# warship_demo_1.net
KiCad netlist of a schematic drawn in Altium Designer
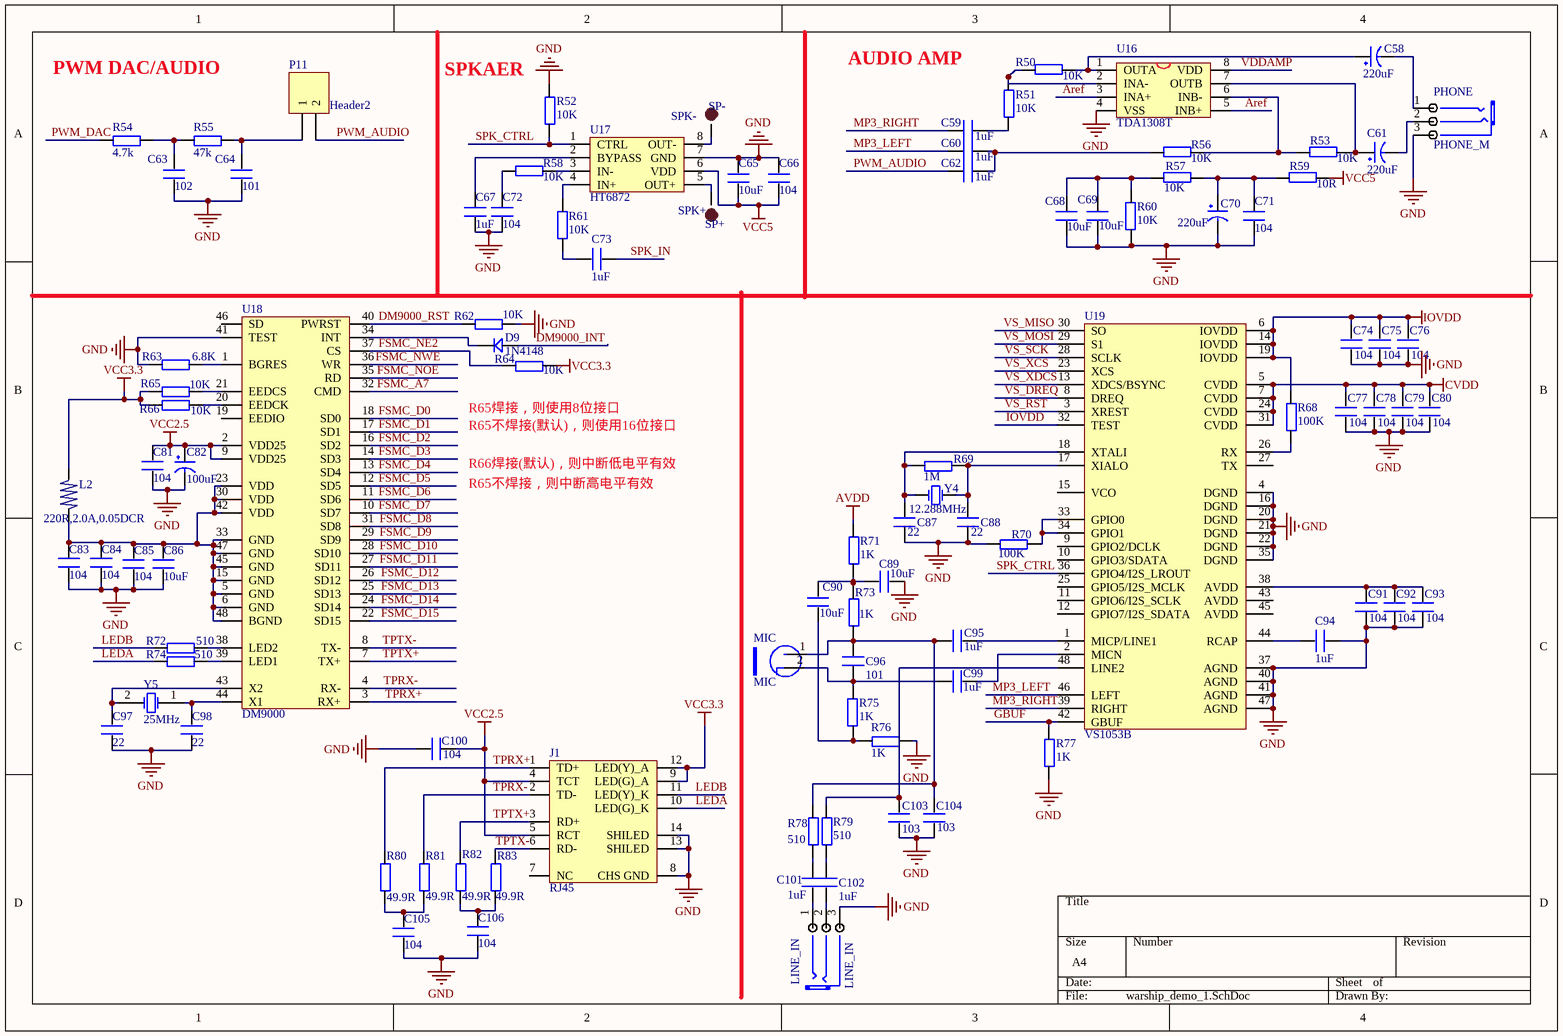
[diagram p0: warship_demo_1.SchDoc]

(export (version "E")
  (design (tool "Eeschema 10.0.6"))
  (components
    (comp (ref "C58") (value "220uF") (footprint "CC6.56.5") (libsource (lib "") (part "CAP_1")))
    (comp (ref "C59") (value "1uF") (footprint "0603P") (libsource (lib "WarShip V3 STM32103封装库") (part "C")))
    (comp (ref "C60") (value "1uF") (footprint "0603P") (libsource (lib "WarShip V3 STM32103封装库") (part "C")))
    (comp (ref "C61") (value "220uF") (footprint "CC6.56.5") (libsource (lib "") (part "CAP_1")))
    (comp (ref "C62") (value "1uF") (footprint "0603P") (libsource (lib "WarShip V3 STM32103封装库") (part "C")))
    (comp (ref "C63") (value "102") (footprint "0603P") (libsource (lib "WarShip V3 STM32103封装库") (part "C")))
    (comp (ref "C64") (value "101") (footprint "0603P") (libsource (lib "WarShip V3 STM32103封装库") (part "C")))
    (comp (ref "C65")
      (value "10uF")
      (footprint "0603P")
      (libsource (lib "WarShip V3 STM32103封装库") (part "C"))
    )
    (comp (ref "C66") (value "104") (footprint "0603P") (libsource (lib "WarShip V3 STM32103封装库") (part "C")))
    (comp (ref "C67") (value "1uF") (footprint "0603P") (libsource (lib "WarShip V3 STM32103封装库") (part "C")))
    (comp (ref "C68")
      (value "10uF")
      (footprint "0603P")
      (libsource (lib "WarShip V3 STM32103封装库") (part "C"))
    )
    (comp (ref "C69")
      (value "10uF")
      (footprint "0603P")
      (libsource (lib "WarShip V3 STM32103封装库") (part "C"))
    )
    (comp (ref "C70")
      (value "220uF")
      (footprint "CC6.56.5")
      (libsource (lib "WarShip V3 STM32103封装库") (part "CAP"))
    )
    (comp (ref "C71") (value "104") (footprint "0603P") (libsource (lib "WarShip V3 STM32103封装库") (part "C")))
    (comp (ref "C72") (value "104") (footprint "0603P") (libsource (lib "WarShip V3 STM32103封装库") (part "C")))
    (comp (ref "C73") (value "1uF") (footprint "0603P") (libsource (lib "WarShip V3 STM32103封装库") (part "C")))
    (comp (ref "C74") (value "104") (footprint "0603P") (libsource (lib "MP3模块封装库") (part "C")))
    (comp (ref "C75") (value "104") (footprint "0603P") (libsource (lib "MP3模块封装库") (part "C")))
    (comp (ref "C76") (value "104") (footprint "0603P") (libsource (lib "MP3模块封装库") (part "C")))
    (comp (ref "C77") (value "104") (footprint "0603P") (libsource (lib "MP3模块封装库") (part "C")))
    (comp (ref "C78") (value "104") (footprint "0603P") (libsource (lib "MP3模块封装库") (part "C")))
    (comp (ref "C79") (value "104") (footprint "0603P") (libsource (lib "MP3模块封装库") (part "C")))
    (comp (ref "C80") (value "104") (footprint "0603P") (libsource (lib "MP3模块封装库") (part "C")))
    (comp (ref "C81") (value "104") (footprint "0603P") (libsource (lib "WarShip V3 STM32103封装库") (part "C")))
    (comp (ref "C82")
      (value "100uF")
      (footprint "CC6.56.5")
      (libsource (lib "WarShip V3 STM32103封装库") (part "CAP"))
    )
    (comp (ref "C83") (value "104") (footprint "0603P") (libsource (lib "WarShip V3 STM32103封装库") (part "C")))
    (comp (ref "C84") (value "104") (footprint "0603P") (libsource (lib "WarShip V3 STM32103封装库") (part "C")))
    (comp (ref "C85") (value "104") (footprint "0603P") (libsource (lib "WarShip V3 STM32103封装库") (part "C")))
    (comp (ref "C86")
      (value "10uF")
      (footprint "0603P")
      (libsource (lib "WarShip V3 STM32103封装库") (part "C"))
    )
    (comp (ref "C87") (value "22") (footprint "0603P") (libsource (lib "MP3模块封装库") (part "C")))
    (comp (ref "C88") (value "22") (footprint "0603P") (libsource (lib "MP3模块封装库") (part "C")))
    (comp (ref "C89") (value "10uF") (footprint "0603P") (libsource (lib "MP3模块封装库") (part "C")))
    (comp (ref "C90") (value "10uF") (footprint "0603P") (libsource (lib "MP3模块封装库") (part "C")))
    (comp (ref "C91") (value "104") (footprint "0603P") (libsource (lib "MP3模块封装库") (part "C")))
    (comp (ref "C92") (value "104") (footprint "0603P") (libsource (lib "MP3模块封装库") (part "C")))
    (comp (ref "C93") (value "104") (footprint "0603P") (libsource (lib "MP3模块封装库") (part "C")))
    (comp (ref "C94") (value "1uF") (footprint "0603P") (libsource (lib "MP3模块封装库") (part "C")))
    (comp (ref "C95") (value "1uF") (footprint "0603P") (libsource (lib "MP3模块封装库") (part "C")))
    (comp (ref "C96") (value "101") (footprint "0603P") (libsource (lib "MP3模块封装库") (part "C")))
    (comp (ref "C97") (value "22") (footprint "0603P") (libsource (lib "WarShip V3 STM32103封装库") (part "C")))
    (comp (ref "C98") (value "22") (footprint "0603P") (libsource (lib "WarShip V3 STM32103封装库") (part "C")))
    (comp (ref "C99") (value "1uF") (footprint "0603P") (libsource (lib "MP3模块封装库") (part "C")))
    (comp (ref "C100")
      (value "104")
      (footprint "0603P")
      (libsource (lib "WarShip V3 STM32103封装库") (part "C"))
    )
    (comp (ref "C101") (value "1uF") (footprint "0603P") (libsource (lib "MP3模块封装库") (part "C")))
    (comp (ref "C102") (value "1uF") (footprint "0603P") (libsource (lib "MP3模块封装库") (part "C")))
    (comp (ref "C103") (value "103") (footprint "0603P") (libsource (lib "MP3模块封装库") (part "C")))
    (comp (ref "C104") (value "103") (footprint "0603P") (libsource (lib "MP3模块封装库") (part "C")))
    (comp (ref "C105")
      (value "104")
      (footprint "0603P")
      (libsource (lib "WarShip V3 STM32103封装库") (part "C"))
    )
    (comp (ref "C106")
      (value "104")
      (footprint "0603P")
      (libsource (lib "WarShip V3 STM32103封装库") (part "C"))
    )
    (comp (ref "D9")
      (value "1N4148")
      (footprint "DIODE_SOP")
      (libsource (lib "WarShip V3 STM32103封装库") (part "D"))
    )
    (comp (ref "J1")
      (value "RJ45")
      (footprint "HR911105A")
      (libsource (lib "WarShip V3 STM32103封装库") (part "HR911105"))
    )
    (comp (ref "L2")
      (value "220R,2.0A,0.05DCR")
      (footprint "0603P")
      (libsource (lib "WarShip V3 STM32103封装库") (part "L"))
    )
    (comp (ref "LINE_IN")
      (value "LINE_IN")
      (footprint "PHONE_ST")
      (libsource (lib "MP3模块封装库") (part "PHONE_M"))
    )
    (comp (ref "MIC") (value "MIC") (footprint "MIC") (libsource (lib "MP3模块封装库") (part "MIC")))
    (comp (ref "P11")
      (value "Header2")
      (footprint "HDR1X2")
      (description "Header, 2-Pin")
      (fields (field (name "PUBLISHER") "Altium Limited"))
      (libsource (lib "WarShip V3 STM32103封装库") (part "Header 2"))
    )
    (comp (ref "PHONE")
      (value "PHONE_M")
      (footprint "PHONE_ST")
      (libsource (lib "WarShip V3 STM32103封装库") (part "PHONE_M"))
    )
    (comp (ref "R50") (value "10K") (footprint "0603P") (libsource (lib "WarShip V3 STM32103封装库") (part "R")))
    (comp (ref "R51") (value "10K") (footprint "0603P") (libsource (lib "WarShip V3 STM32103封装库") (part "R")))
    (comp (ref "R52") (value "10K") (footprint "0603P") (libsource (lib "WarShip V3 STM32103封装库") (part "R")))
    (comp (ref "R53") (value "10K") (footprint "0603P") (libsource (lib "WarShip V3 STM32103封装库") (part "R")))
    (comp (ref "R54")
      (value "4.7k")
      (footprint "0603P")
      (libsource (lib "WarShip V3 STM32103封装库") (part "R"))
    )
    (comp (ref "R55") (value "47k") (footprint "0603P") (libsource (lib "WarShip V3 STM32103封装库") (part "R")))
    (comp (ref "R56") (value "10K") (footprint "0603P") (libsource (lib "WarShip V3 STM32103封装库") (part "R")))
    (comp (ref "R57") (value "10K") (footprint "0603P") (libsource (lib "WarShip V3 STM32103封装库") (part "R")))
    (comp (ref "R58") (value "10K") (footprint "0603P") (libsource (lib "WarShip V3 STM32103封装库") (part "R")))
    (comp (ref "R59") (value "10R") (footprint "0603P") (libsource (lib "WarShip V3 STM32103封装库") (part "R")))
    (comp (ref "R60") (value "10K") (footprint "0603P") (libsource (lib "WarShip V3 STM32103封装库") (part "R")))
    (comp (ref "R61") (value "10K") (footprint "0603P") (libsource (lib "WarShip V3 STM32103封装库") (part "R")))
    (comp (ref "R62") (value "10K") (footprint "0603P") (libsource (lib "WarShip V3 STM32103封装库") (part "R")))
    (comp (ref "R63")
      (value "6.8K")
      (footprint "0603P")
      (libsource (lib "WarShip V3 STM32103封装库") (part "R"))
    )
    (comp (ref "R64") (value "10K") (footprint "0603P") (libsource (lib "WarShip V3 STM32103封装库") (part "R")))
    (comp (ref "R65") (value "10K") (footprint "0603P") (libsource (lib "WarShip V3 STM32103封装库") (part "R")))
    (comp (ref "R66") (value "10K") (footprint "0603P") (libsource (lib "WarShip V3 STM32103封装库") (part "R")))
    (comp (ref "R68") (value "100K") (footprint "0603P") (libsource (lib "MP3模块封装库") (part "R")))
    (comp (ref "R69") (value "1M") (footprint "0603P") (libsource (lib "MP3模块封装库") (part "R")))
    (comp (ref "R70") (value "100K") (footprint "0603P") (libsource (lib "MP3模块封装库") (part "R")))
    (comp (ref "R71") (value "1K") (footprint "0603P") (libsource (lib "MP3模块封装库") (part "R")))
    (comp (ref "R72") (value "510") (footprint "0603P") (libsource (lib "WarShip V3 STM32103封装库") (part "R")))
    (comp (ref "R73") (value "1K") (footprint "0603P") (libsource (lib "MP3模块封装库") (part "R")))
    (comp (ref "R74") (value "510") (footprint "0603P") (libsource (lib "WarShip V3 STM32103封装库") (part "R")))
    (comp (ref "R75") (value "1K") (footprint "0603P") (libsource (lib "MP3模块封装库") (part "R")))
    (comp (ref "R76") (value "1K") (footprint "0603P") (libsource (lib "MP3模块封装库") (part "R")))
    (comp (ref "R77") (value "1K") (footprint "0603P") (libsource (lib "MP3模块封装库") (part "R")))
    (comp (ref "R78") (value "510") (footprint "0603P") (libsource (lib "MP3模块封装库") (part "R")))
    (comp (ref "R79") (value "510") (footprint "0603P") (libsource (lib "MP3模块封装库") (part "R")))
    (comp (ref "R80")
      (value "49.9R")
      (footprint "0603P")
      (libsource (lib "WarShip V3 STM32103封装库") (part "R"))
    )
    (comp (ref "R81")
      (value "49.9R")
      (footprint "0603P")
      (libsource (lib "WarShip V3 STM32103封装库") (part "R"))
    )
    (comp (ref "R82")
      (value "49.9R")
      (footprint "0603P")
      (libsource (lib "WarShip V3 STM32103封装库") (part "R"))
    )
    (comp (ref "R83")
      (value "49.9R")
      (footprint "0603P")
      (libsource (lib "WarShip V3 STM32103封装库") (part "R"))
    )
    (comp (ref "SP+")
      (value "SPK+")
      (footprint "TP-1.5")
      (description "测试点")
      (libsource (lib "WarShip V3 STM32103封装库") (part "TEST-POINT"))
    )
    (comp (ref "SP-")
      (value "SPK-")
      (footprint "TP-1.5")
      (description "测试点")
      (libsource (lib "WarShip V3 STM32103封装库") (part "TEST-POINT"))
    )
    (comp (ref "U16")
      (value "TDA1308T")
      (footprint "SOP-8")
      (libsource (lib "WarShip V3 STM32103封装库") (part "TDA1308"))
    )
    (comp (ref "U17")
      (value "HT6872")
      (footprint "SOP-8")
      (description "HT6871")
      (libsource (lib "WarShip V3 STM32103封装库") (part "HT6871"))
    )
    (comp (ref "U18")
      (value "DM9000")
      (footprint "mTQFP48")
      (libsource (lib "WarShip V3 STM32103封装库") (part "DM9000A"))
    )
    (comp (ref "U19")
      (value "VS1053B")
      (footprint "mTQFP48")
      (libsource (lib "WarShip V3 STM32103封装库") (part "VS1053"))
    )
    (comp (ref "Y4")
      (value "12.288MHz")
      (footprint "XTAL_US")
      (description "Crystal Oscillator")
      (fields (field (name "PUBLISHER") "Altium Limited"))
      (libsource (lib "MP3模块封装库") (part "XTAL"))
    )
    (comp (ref "Y5")
      (value "25MHz")
      (footprint "XTAL_US")
      (description "Crystal Oscillator")
      (fields (field (name "PUBLISHER") "Altium Limited"))
      (libsource (lib "ENC28J60网络模块封装库") (part "XTAL"))
    )
  )
  (nets
    (net (code "1") (name "/Aref") (class "Default")
      (node (ref "U16") (pin "3") (pinfunction "INA+_3") (pintype "passive"))
      (node (ref "U16") (pin "5") (pinfunction "INB+_5") (pintype "passive"))
    )
    (net (code "2") (name "/DM9000_INT") (class "Default") (node (ref "D9") (pin "1") (pintype "passive")))
    (net (code "3") (name "/DM9000_RST") (class "Default")
      (node (ref "R62") (pin "1") (pintype "passive"))
      (node (ref "U18") (pin "40") (pinfunction "PWRST_40") (pintype "passive"))
    )
    (net (code "4") (name "/FSMC_A7") (class "Default")
      (node (ref "U18") (pin "32") (pinfunction "CMD_32") (pintype "passive"))
    )
    (net (code "5") (name "/FSMC_D0") (class "Default")
      (node (ref "U18") (pin "18") (pinfunction "SD0_18") (pintype "passive"))
    )
    (net (code "6") (name "/FSMC_D1") (class "Default")
      (node (ref "U18") (pin "17") (pinfunction "SD1_17") (pintype "passive"))
    )
    (net (code "7") (name "/FSMC_D2") (class "Default")
      (node (ref "U18") (pin "16") (pinfunction "SD2_16") (pintype "passive"))
    )
    (net (code "8") (name "/FSMC_D3") (class "Default")
      (node (ref "U18") (pin "14") (pinfunction "SD3_14") (pintype "passive"))
    )
    (net (code "9") (name "/FSMC_D4") (class "Default")
      (node (ref "U18") (pin "13") (pinfunction "SD4_13") (pintype "passive"))
    )
    (net (code "10") (name "/FSMC_D5") (class "Default")
      (node (ref "U18") (pin "12") (pinfunction "SD5_12") (pintype "passive"))
    )
    (net (code "11") (name "/FSMC_D6") (class "Default")
      (node (ref "U18") (pin "11") (pinfunction "SD6_11") (pintype "passive"))
    )
    (net (code "12") (name "/FSMC_D7") (class "Default")
      (node (ref "U18") (pin "10") (pinfunction "SD7_10") (pintype "passive"))
    )
    (net (code "13") (name "/FSMC_D8") (class "Default")
      (node (ref "U18") (pin "31") (pinfunction "SD8_31") (pintype "passive"))
    )
    (net (code "14") (name "/FSMC_D9") (class "Default")
      (node (ref "U18") (pin "29") (pinfunction "SD9_29") (pintype "passive"))
    )
    (net (code "15") (name "/FSMC_D10") (class "Default")
      (node (ref "U18") (pin "28") (pinfunction "SD10_28") (pintype "passive"))
    )
    (net (code "16") (name "/FSMC_D11") (class "Default")
      (node (ref "U18") (pin "27") (pinfunction "SD11_27") (pintype "passive"))
    )
    (net (code "17") (name "/FSMC_D12") (class "Default")
      (node (ref "U18") (pin "26") (pinfunction "SD12_26") (pintype "passive"))
    )
    (net (code "18") (name "/FSMC_D13") (class "Default")
      (node (ref "U18") (pin "25") (pinfunction "SD13_25") (pintype "passive"))
    )
    (net (code "19") (name "/FSMC_D14") (class "Default")
      (node (ref "U18") (pin "24") (pinfunction "SD14_24") (pintype "passive"))
    )
    (net (code "20") (name "/FSMC_D15") (class "Default")
      (node (ref "U18") (pin "22") (pinfunction "SD15_22") (pintype "passive"))
    )
    (net (code "21") (name "/FSMC_NE2") (class "Default")
      (node (ref "R64") (pin "1") (pintype "passive"))
      (node (ref "U18") (pin "37") (pinfunction "CS_37") (pintype "passive"))
    )
    (net (code "22") (name "/FSMC_NOE") (class "Default")
      (node (ref "U18") (pin "35") (pinfunction "RD_35") (pintype "passive"))
    )
    (net (code "23") (name "/FSMC_NWE") (class "Default")
      (node (ref "U18") (pin "36") (pinfunction "WR_36") (pintype "passive"))
    )
    (net (code "24") (name "/GBUF") (class "Default")
      (node (ref "R77") (pin "2") (pintype "passive"))
      (node (ref "U19") (pin "42") (pinfunction "GBUF_42") (pintype "passive"))
    )
    (net (code "25") (name "/LEDA") (class "Default")
      (node (ref "J1") (pin "10") (pinfunction "LED(G)_K_10") (pintype "passive"))
      (node (ref "R74") (pin "1") (pintype "passive"))
    )
    (net (code "26") (name "/LEDB") (class "Default")
      (node (ref "J1") (pin "11") (pinfunction "LED(Y)_K_11") (pintype "passive"))
      (node (ref "R72") (pin "1") (pintype "passive"))
    )
    (net (code "27") (name "/MP3_LEFT") (class "Default")
      (node (ref "C60") (pin "2") (pintype "passive"))
      (node (ref "U19") (pin "46") (pinfunction "LEFT_46") (pintype "passive"))
    )
    (net (code "28") (name "/MP3_RIGHT") (class "Default")
      (node (ref "C59") (pin "2") (pintype "passive"))
      (node (ref "U19") (pin "39") (pinfunction "RIGHT_39") (pintype "passive"))
    )
    (net (code "29") (name "/PWM_AUDIO") (class "Default")
      (node (ref "C62") (pin "2") (pintype "passive"))
      (node (ref "P11") (pin "2") (pinfunction "2_2") (pintype "passive"))
    )
    (net (code "30") (name "/PWM_DAC") (class "Default") (node (ref "R54") (pin "1") (pintype "passive")))
    (net (code "31") (name "/SPK_CTRL") (class "Default")
      (node (ref "R52") (pin "1") (pintype "passive"))
      (node (ref "U17") (pin "1") (pinfunction "CTRL_1") (pintype "passive"))
      (node (ref "U19") (pin "36") (pinfunction "GPIO4/I2S_LROUT_36") (pintype "passive"))
    )
    (net (code "32") (name "/SPK_IN") (class "Default") (node (ref "C73") (pin "1") (pintype "passive")))
    (net (code "33") (name "/TPRX+") (class "Default")
      (node (ref "J1") (pin "1") (pinfunction "TD+_1") (pintype "passive"))
      (node (ref "R80") (pin "2") (pintype "passive"))
      (node (ref "U18") (pin "3") (pinfunction "RX+_3") (pintype "passive"))
    )
    (net (code "34") (name "/TPRX-") (class "Default")
      (node (ref "J1") (pin "2") (pinfunction "TD-_2") (pintype "passive"))
      (node (ref "R81") (pin "2") (pintype "passive"))
      (node (ref "U18") (pin "4") (pinfunction "RX-_4") (pintype "passive"))
    )
    (net (code "35") (name "/TPTX+") (class "Default")
      (node (ref "J1") (pin "3") (pinfunction "RD+_3") (pintype "passive"))
      (node (ref "R82") (pin "2") (pintype "passive"))
      (node (ref "U18") (pin "7") (pinfunction "TX+_7") (pintype "passive"))
    )
    (net (code "36") (name "/TPTX-") (class "Default")
      (node (ref "J1") (pin "6") (pinfunction "RD-_6") (pintype "passive"))
      (node (ref "R83") (pin "2") (pintype "passive"))
      (node (ref "U18") (pin "8") (pinfunction "TX-_8") (pintype "passive"))
    )
    (net (code "37") (name "/VDDAMP") (class "Default")
      (node (ref "U16") (pin "8") (pinfunction "VDD_8") (pintype "passive"))
    )
    (net (code "38") (name "/VS_DREQ") (class "Default")
      (node (ref "U19") (pin "8") (pinfunction "DREQ_8") (pintype "passive"))
    )
    (net (code "39") (name "/VS_MISO") (class "Default")
      (node (ref "U19") (pin "30") (pinfunction "SO_30") (pintype "passive"))
    )
    (net (code "40") (name "/VS_MOSI") (class "Default")
      (node (ref "U19") (pin "29") (pinfunction "S1_29") (pintype "passive"))
    )
    (net (code "41") (name "/VS_RST") (class "Default")
      (node (ref "U19") (pin "3") (pinfunction "XREST_3") (pintype "passive"))
    )
    (net (code "42") (name "/VS_SCK") (class "Default")
      (node (ref "U19") (pin "28") (pinfunction "SCLK_28") (pintype "passive"))
    )
    (net (code "43") (name "/VS_XCS") (class "Default")
      (node (ref "U19") (pin "23") (pinfunction "XCS_23") (pintype "passive"))
    )
    (net (code "44") (name "/VS_XDCS") (class "Default")
      (node (ref "U19") (pin "13") (pinfunction "XDCS/BSYNC_13") (pintype "passive"))
    )
    (net (code "45") (name "AVDD") (class "Default") (node (ref "R71") (pin "2") (pintype "passive")))
    (net (code "46") (name "CVDD") (class "Default")
      (node (ref "C77") (pin "2") (pintype "passive"))
      (node (ref "C78") (pin "2") (pintype "passive"))
      (node (ref "C79") (pin "2") (pintype "passive"))
      (node (ref "C80") (pin "2") (pintype "passive"))
      (node (ref "U19") (pin "24") (pinfunction "CVDD_24") (pintype "passive"))
      (node (ref "U19") (pin "31") (pinfunction "CVDD_31") (pintype "passive"))
      (node (ref "U19") (pin "5") (pinfunction "CVDD_5") (pintype "passive"))
      (node (ref "U19") (pin "7") (pinfunction "CVDD_7") (pintype "passive"))
    )
    (net (code "47") (name "GND") (class "Default")
      (node (ref "C100") (pin "2") (pintype "passive"))
      (node (ref "C103") (pin "1") (pintype "passive"))
      (node (ref "C104") (pin "1") (pintype "passive"))
      (node (ref "C105") (pin "1") (pintype "passive"))
      (node (ref "C106") (pin "1") (pintype "passive"))
      (node (ref "C63") (pin "1") (pintype "passive"))
      (node (ref "C64") (pin "1") (pintype "passive"))
      (node (ref "C65") (pin "1") (pintype "passive"))
      (node (ref "C66") (pin "1") (pintype "passive"))
      (node (ref "C67") (pin "1") (pintype "passive"))
      (node (ref "C68") (pin "2") (pintype "passive"))
      (node (ref "C69") (pin "2") (pintype "passive"))
      (node (ref "C70") (pin "2") (pinfunction "GND_2") (pintype "passive"))
      (node (ref "C71") (pin "2") (pintype "passive"))
      (node (ref "C72") (pin "1") (pintype "passive"))
      (node (ref "C74") (pin "1") (pintype "passive"))
      (node (ref "C75") (pin "1") (pintype "passive"))
      (node (ref "C76") (pin "1") (pintype "passive"))
      (node (ref "C77") (pin "1") (pintype "passive"))
      (node (ref "C78") (pin "1") (pintype "passive"))
      (node (ref "C79") (pin "1") (pintype "passive"))
      (node (ref "C80") (pin "1") (pintype "passive"))
      (node (ref "C81") (pin "1") (pintype "passive"))
      (node (ref "C82") (pin "2") (pinfunction "GND_2") (pintype "passive"))
      (node (ref "C83") (pin "1") (pintype "passive"))
      (node (ref "C84") (pin "1") (pintype "passive"))
      (node (ref "C85") (pin "1") (pintype "passive"))
      (node (ref "C86") (pin "1") (pintype "passive"))
      (node (ref "C87") (pin "1") (pintype "passive"))
      (node (ref "C88") (pin "2") (pintype "passive"))
      (node (ref "C89") (pin "1") (pintype "passive"))
      (node (ref "C91") (pin "1") (pintype "passive"))
      (node (ref "C92") (pin "1") (pintype "passive"))
      (node (ref "C93") (pin "1") (pintype "passive"))
      (node (ref "C94") (pin "1") (pintype "passive"))
      (node (ref "C97") (pin "1") (pintype "passive"))
      (node (ref "C98") (pin "1") (pintype "passive"))
      (node (ref "J1") (pin "13") (pinfunction "SHILED_13") (pintype "passive"))
      (node (ref "J1") (pin "14") (pinfunction "SHILED_14") (pintype "passive"))
      (node (ref "J1") (pin "8") (pinfunction "CHS_GND_8") (pintype "passive"))
      (node (ref "LINE_IN") (pin "3") (pinfunction "COM_3") (pintype "passive"))
      (node (ref "PHONE") (pin "3") (pinfunction "COM_3") (pintype "passive"))
      (node (ref "R52") (pin "2") (pintype "passive"))
      (node (ref "R60") (pin "2") (pintype "passive"))
      (node (ref "R62") (pin "2") (pintype "passive"))
      (node (ref "R63") (pin "1") (pintype "passive"))
      (node (ref "R70") (pin "1") (pintype "passive"))
      (node (ref "R76") (pin "2") (pintype "passive"))
      (node (ref "R77") (pin "1") (pintype "passive"))
      (node (ref "U16") (pin "4") (pinfunction "VSS_4") (pintype "passive"))
      (node (ref "U17") (pin "7") (pinfunction "GND_7") (pintype "passive"))
      (node (ref "U18") (pin "41") (pinfunction "TEST_41") (pintype "passive"))
      (node (ref "U19") (pin "16") (pinfunction "DGND_16") (pintype "passive"))
      (node (ref "U19") (pin "20") (pinfunction "DGND_20") (pintype "passive"))
      (node (ref "U19") (pin "21") (pinfunction "DGND_21") (pintype "passive"))
      (node (ref "U19") (pin "22") (pinfunction "DGND_22") (pintype "passive"))
      (node (ref "U19") (pin "35") (pinfunction "DGND_35") (pintype "passive"))
      (node (ref "U19") (pin "37") (pinfunction "AGND_37") (pintype "passive"))
      (node (ref "U19") (pin "4") (pinfunction "DGND_4") (pintype "passive"))
      (node (ref "U19") (pin "40") (pinfunction "AGND_40") (pintype "passive"))
      (node (ref "U19") (pin "41") (pinfunction "AGND_41") (pintype "passive"))
      (node (ref "U19") (pin "47") (pinfunction "AGND_47") (pintype "passive"))
    )
    (net (code "48") (name "IOVDD") (class "Default")
      (node (ref "C74") (pin "2") (pintype "passive"))
      (node (ref "C75") (pin "2") (pintype "passive"))
      (node (ref "C76") (pin "2") (pintype "passive"))
      (node (ref "R68") (pin "2") (pintype "passive"))
      (node (ref "U19") (pin "14") (pinfunction "IOVDD_14") (pintype "passive"))
      (node (ref "U19") (pin "19") (pinfunction "IOVDD_19") (pintype "passive"))
      (node (ref "U19") (pin "32") (pinfunction "TEST_32") (pintype "passive"))
      (node (ref "U19") (pin "6") (pinfunction "IOVDD_6") (pintype "passive"))
    )
    (net (code "49") (name "Net-(C58-GND)") (class "Default")
      (node (ref "C58") (pin "2") (pinfunction "GND_2") (pintype "passive"))
      (node (ref "PHONE") (pin "1") (pinfunction "CHL_1") (pintype "passive"))
    )
    (net (code "50") (name "Net-(C58-VCC)") (class "Default")
      (node (ref "C58") (pin "1") (pinfunction "VCC_1") (pintype "passive"))
      (node (ref "R50") (pin "1") (pintype "passive"))
      (node (ref "U16") (pin "1") (pinfunction "OUTA_1") (pintype "passive"))
    )
    (net (code "51") (name "Net-(C59-Pad1)") (class "Default")
      (node (ref "C59") (pin "1") (pintype "passive"))
      (node (ref "R51") (pin "1") (pintype "passive"))
    )
    (net (code "52") (name "Net-(C60-Pad1)") (class "Default")
      (node (ref "C60") (pin "1") (pintype "passive"))
      (node (ref "C62") (pin "1") (pintype "passive"))
      (node (ref "R56") (pin "2") (pintype "passive"))
    )
    (net (code "53") (name "Net-(C61-GND)") (class "Default")
      (node (ref "C61") (pin "2") (pinfunction "GND_2") (pintype "passive"))
      (node (ref "PHONE") (pin "2") (pinfunction "CHR_2") (pintype "passive"))
    )
    (net (code "54") (name "Net-(C61-VCC)") (class "Default")
      (node (ref "C61") (pin "1") (pinfunction "VCC_1") (pintype "passive"))
      (node (ref "R53") (pin "1") (pintype "passive"))
      (node (ref "U16") (pin "7") (pinfunction "OUTB_7") (pintype "passive"))
    )
    (net (code "55") (name "Net-(C63-Pad2)") (class "Default")
      (node (ref "C63") (pin "2") (pintype "passive"))
      (node (ref "R54") (pin "2") (pintype "passive"))
      (node (ref "R55") (pin "1") (pintype "passive"))
    )
    (net (code "56") (name "Net-(C64-Pad2)") (class "Default")
      (node (ref "C64") (pin "2") (pintype "passive"))
      (node (ref "P11") (pin "1") (pinfunction "1_1") (pintype "passive"))
      (node (ref "R55") (pin "2") (pintype "passive"))
    )
    (net (code "57") (name "Net-(C68-Pad1)") (class "Default")
      (node (ref "C68") (pin "1") (pintype "passive"))
      (node (ref "C69") (pin "1") (pintype "passive"))
      (node (ref "R57") (pin "2") (pintype "passive"))
      (node (ref "R60") (pin "1") (pintype "passive"))
    )
    (net (code "58") (name "Net-(C70-VCC)") (class "Default")
      (node (ref "C70") (pin "1") (pinfunction "VCC_1") (pintype "passive"))
      (node (ref "C71") (pin "1") (pintype "passive"))
      (node (ref "R57") (pin "1") (pintype "passive"))
      (node (ref "R59") (pin "2") (pintype "passive"))
    )
    (net (code "59") (name "Net-(C72-Pad2)") (class "Default")
      (node (ref "C72") (pin "2") (pintype "passive"))
      (node (ref "R58") (pin "2") (pintype "passive"))
    )
    (net (code "60") (name "Net-(C73-Pad2)") (class "Default")
      (node (ref "C73") (pin "2") (pintype "passive"))
      (node (ref "R61") (pin "2") (pintype "passive"))
    )
    (net (code "61") (name "Net-(C89-Pad2)") (class "Default")
      (node (ref "C89") (pin "2") (pintype "passive"))
      (node (ref "C90") (pin "1") (pintype "passive"))
      (node (ref "R71") (pin "1") (pintype "passive"))
      (node (ref "R73") (pin "2") (pintype "passive"))
    )
    (net (code "62") (name "Net-(C90-Pad2)") (class "Default")
      (node (ref "C90") (pin "2") (pintype "passive"))
      (node (ref "R75") (pin "2") (pintype "passive"))
      (node (ref "R76") (pin "1") (pintype "passive"))
    )
    (net (code "63") (name "Net-(C91-Pad2)") (class "Default")
      (node (ref "C91") (pin "2") (pintype "passive"))
      (node (ref "C92") (pin "2") (pintype "passive"))
      (node (ref "C93") (pin "2") (pintype "passive"))
      (node (ref "U19") (pin "38") (pinfunction "AVDD_38") (pintype "passive"))
    )
    (net (code "64") (name "Net-(C101-Pad2)") (class "Default")
      (node (ref "C101") (pin "2") (pintype "passive"))
      (node (ref "R78") (pin "1") (pintype "passive"))
    )
    (net (code "65") (name "Net-(C102-Pad2)") (class "Default")
      (node (ref "C102") (pin "2") (pintype "passive"))
      (node (ref "R79") (pin "1") (pintype "passive"))
    )
    (net (code "66") (name "Net-(C105-Pad2)") (class "Default")
      (node (ref "C105") (pin "2") (pintype "passive"))
      (node (ref "R80") (pin "1") (pintype "passive"))
      (node (ref "R81") (pin "1") (pintype "passive"))
    )
    (net (code "67") (name "Net-(C106-Pad2)") (class "Default")
      (node (ref "C106") (pin "2") (pintype "passive"))
      (node (ref "R82") (pin "1") (pintype "passive"))
      (node (ref "R83") (pin "1") (pintype "passive"))
    )
    (net (code "68") (name "Net-(LINE_IN-CHL)") (class "Default")
      (node (ref "C101") (pin "1") (pintype "passive"))
      (node (ref "LINE_IN") (pin "1") (pinfunction "CHL_1") (pintype "passive"))
    )
    (net (code "69") (name "Net-(LINE_IN-CHR)") (class "Default")
      (node (ref "C102") (pin "1") (pintype "passive"))
      (node (ref "LINE_IN") (pin "2") (pinfunction "CHR_2") (pintype "passive"))
    )
    (net (code "70") (name "Net-(MIC-GND)") (class "Default")
      (node (ref "C96") (pin "1") (pintype "passive"))
      (node (ref "C99") (pin "1") (pintype "passive"))
      (node (ref "MIC") (pin "2") (pinfunction "GND_2") (pintype "passive"))
      (node (ref "R75") (pin "1") (pintype "passive"))
    )
    (net (code "71") (name "Net-(MIC-VCC)") (class "Default")
      (node (ref "C104") (pin "2") (pintype "passive"))
      (node (ref "C95") (pin "1") (pintype "passive"))
      (node (ref "C96") (pin "2") (pintype "passive"))
      (node (ref "MIC") (pin "1") (pinfunction "VCC_1") (pintype "passive"))
      (node (ref "R73") (pin "1") (pintype "passive"))
      (node (ref "R78") (pin "2") (pintype "passive"))
    )
    (net (code "72") (name "Net-(U16-INA-)") (class "Default")
      (node (ref "R50") (pin "2") (pintype "passive"))
      (node (ref "R51") (pin "2") (pintype "passive"))
      (node (ref "U16") (pin "2") (pinfunction "INA-_2") (pintype "passive"))
    )
    (net (code "73") (name "Net-(U16-INB-)") (class "Default")
      (node (ref "R53") (pin "2") (pintype "passive"))
      (node (ref "R56") (pin "1") (pintype "passive"))
      (node (ref "U16") (pin "6") (pinfunction "INB-_6") (pintype "passive"))
    )
    (net (code "74") (name "Net-(U17-BYPASS)") (class "Default")
      (node (ref "C67") (pin "2") (pintype "passive"))
      (node (ref "U17") (pin "2") (pinfunction "BYPASS_2") (pintype "passive"))
    )
    (net (code "75") (name "Net-(U17-IN+)") (class "Default")
      (node (ref "R61") (pin "1") (pintype "passive"))
      (node (ref "U17") (pin "4") (pinfunction "IN+_4") (pintype "passive"))
    )
    (net (code "76") (name "Net-(U17-IN-)") (class "Default")
      (node (ref "R58") (pin "1") (pintype "passive"))
      (node (ref "U17") (pin "3") (pinfunction "IN-_3") (pintype "passive"))
    )
    (net (code "77") (name "Net-(U17-OUT+)") (class "Default")
      (node (ref "SP+") (pin "1") (pinfunction "1_1") (pintype "passive"))
      (node (ref "U17") (pin "5") (pinfunction "OUT+_5") (pintype "passive"))
    )
    (net (code "78") (name "Net-(U17-OUT-)") (class "Default")
      (node (ref "SP-") (pin "1") (pinfunction "1_1") (pintype "passive"))
      (node (ref "U17") (pin "8") (pinfunction "OUT-_8") (pintype "passive"))
    )
    (net (code "79") (name "Net-(U18-BGND)") (class "Default")
      (node (ref "C83") (pin "2") (pintype "passive"))
      (node (ref "C84") (pin "2") (pintype "passive"))
      (node (ref "C85") (pin "2") (pintype "passive"))
      (node (ref "C86") (pin "2") (pintype "passive"))
      (node (ref "L2") (pin "2") (pintype "passive"))
      (node (ref "U18") (pin "15") (pinfunction "GND_15") (pintype "passive"))
      (node (ref "U18") (pin "23") (pinfunction "VDD_23") (pintype "passive"))
      (node (ref "U18") (pin "30") (pinfunction "VDD_30") (pintype "passive"))
      (node (ref "U18") (pin "33") (pinfunction "GND_33") (pintype "passive"))
      (node (ref "U18") (pin "42") (pinfunction "VDD_42") (pintype "passive"))
      (node (ref "U18") (pin "45") (pinfunction "GND_45") (pintype "passive"))
      (node (ref "U18") (pin "47") (pinfunction "GND_47") (pintype "passive"))
      (node (ref "U18") (pin "48") (pinfunction "BGND_48") (pintype "passive"))
      (node (ref "U18") (pin "5") (pinfunction "GND_5") (pintype "passive"))
      (node (ref "U18") (pin "6") (pinfunction "GND_6") (pintype "passive"))
    )
    (net (code "80") (name "Net-(U18-BGRES)") (class "Default")
      (node (ref "R63") (pin "2") (pintype "passive"))
      (node (ref "U18") (pin "1") (pinfunction "BGRES_1") (pintype "passive"))
    )
    (net (code "81") (name "Net-(U18-EEDCK)") (class "Default")
      (node (ref "R66") (pin "2") (pintype "passive"))
      (node (ref "U18") (pin "20") (pinfunction "EEDCK_20") (pintype "passive"))
    )
    (net (code "82") (name "Net-(U18-EEDCS)") (class "Default")
      (node (ref "R65") (pin "2") (pintype "passive"))
      (node (ref "U18") (pin "21") (pinfunction "EEDCS_21") (pintype "passive"))
    )
    (net (code "83") (name "Net-(U18-INT)") (class "Default")
      (node (ref "D9") (pin "2") (pintype "passive"))
      (node (ref "U18") (pin "34") (pinfunction "INT_34") (pintype "passive"))
    )
    (net (code "84") (name "Net-(U18-LED1)") (class "Default")
      (node (ref "R74") (pin "2") (pintype "passive"))
      (node (ref "U18") (pin "39") (pinfunction "LED1_39") (pintype "passive"))
    )
    (net (code "85") (name "Net-(U18-LED2)") (class "Default")
      (node (ref "R72") (pin "2") (pintype "passive"))
      (node (ref "U18") (pin "38") (pinfunction "LED2_38") (pintype "passive"))
    )
    (net (code "86") (name "Net-(U18-X1)") (class "Default")
      (node (ref "C98") (pin "2") (pintype "passive"))
      (node (ref "U18") (pin "44") (pinfunction "X1_44") (pintype "passive"))
      (node (ref "Y5") (pin "1") (pinfunction "OSC1_1") (pintype "passive"))
    )
    (net (code "87") (name "Net-(U18-X2)") (class "Default")
      (node (ref "C97") (pin "2") (pintype "passive"))
      (node (ref "U18") (pin "43") (pinfunction "X2_43") (pintype "passive"))
      (node (ref "Y5") (pin "2") (pinfunction "OSC2_2") (pintype "passive"))
    )
    (net (code "88") (name "Net-(U19-GPIO0)") (class "Default")
      (node (ref "R70") (pin "2") (pintype "passive"))
      (node (ref "U19") (pin "33") (pinfunction "GPIO0_33") (pintype "passive"))
      (node (ref "U19") (pin "34") (pinfunction "GPIO1_34") (pintype "passive"))
    )
    (net (code "89") (name "Net-(U19-LINE2)") (class "Default")
      (node (ref "C103") (pin "2") (pintype "passive"))
      (node (ref "R79") (pin "2") (pintype "passive"))
      (node (ref "U19") (pin "48") (pinfunction "LINE2_48") (pintype "passive"))
    )
    (net (code "90") (name "Net-(U19-MICN)") (class "Default")
      (node (ref "C99") (pin "2") (pintype "passive"))
      (node (ref "U19") (pin "2") (pinfunction "MICN_2") (pintype "passive"))
    )
    (net (code "91") (name "Net-(U19-MICP{slash}LINE1)") (class "Default")
      (node (ref "C95") (pin "2") (pintype "passive"))
      (node (ref "U19") (pin "1") (pinfunction "MICP/LINE1_1") (pintype "passive"))
    )
    (net (code "92") (name "Net-(U19-RCAP)") (class "Default")
      (node (ref "C94") (pin "2") (pintype "passive"))
      (node (ref "U19") (pin "44") (pinfunction "RCAP_44") (pintype "passive"))
    )
    (net (code "93") (name "Net-(U19-RX)") (class "Default")
      (node (ref "R68") (pin "1") (pintype "passive"))
      (node (ref "U19") (pin "26") (pinfunction "RX_26") (pintype "passive"))
    )
    (net (code "94") (name "Net-(U19-XIALO)") (class "Default")
      (node (ref "C88") (pin "1") (pintype "passive"))
      (node (ref "R69") (pin "2") (pintype "passive"))
      (node (ref "U19") (pin "17") (pinfunction "XIALO_17") (pintype "passive"))
      (node (ref "Y4") (pin "2") (pinfunction "OSC2_2") (pintype "passive"))
    )
    (net (code "95") (name "Net-(U19-XTALI)") (class "Default")
      (node (ref "C87") (pin "2") (pintype "passive"))
      (node (ref "R69") (pin "1") (pintype "passive"))
      (node (ref "U19") (pin "18") (pinfunction "XTALI_18") (pintype "passive"))
      (node (ref "Y4") (pin "1") (pinfunction "OSC1_1") (pintype "passive"))
    )
    (net (code "96") (name "VCC2.5") (class "Default")
      (node (ref "C100") (pin "1") (pintype "passive"))
      (node (ref "C81") (pin "2") (pintype "passive"))
      (node (ref "C82") (pin "1") (pinfunction "VCC_1") (pintype "passive"))
      (node (ref "J1") (pin "4") (pinfunction "TCT_4") (pintype "passive"))
      (node (ref "J1") (pin "5") (pinfunction "RCT_5") (pintype "passive"))
      (node (ref "U18") (pin "2") (pinfunction "VDD25_2") (pintype "passive"))
      (node (ref "U18") (pin "9") (pinfunction "VDD25_9") (pintype "passive"))
    )
    (net (code "97") (name "VCC3.3") (class "Default")
      (node (ref "J1") (pin "12") (pinfunction "LED(Y)_A_12") (pintype "passive"))
      (node (ref "J1") (pin "9") (pinfunction "LED(G)_A_9") (pintype "passive"))
      (node (ref "L2") (pin "1") (pintype "passive"))
      (node (ref "R64") (pin "2") (pintype "passive"))
      (node (ref "R65") (pin "1") (pintype "passive"))
      (node (ref "R66") (pin "1") (pintype "passive"))
    )
    (net (code "98") (name "VCC5") (class "Default")
      (node (ref "C65") (pin "2") (pintype "passive"))
      (node (ref "C66") (pin "2") (pintype "passive"))
      (node (ref "R59") (pin "1") (pintype "passive"))
      (node (ref "U17") (pin "6") (pinfunction "VDD_6") (pintype "passive"))
    )
    (net (code "99") (name "unconnected-(J1-NC-Pad7)") (class "Default")
      (node (ref "J1") (pin "7") (pinfunction "NC_7") (pintype "passive"))
    )
    (net (code "100") (name "unconnected-(U18-EEDIO-Pad19)") (class "Default")
      (node (ref "U18") (pin "19") (pinfunction "EEDIO_19") (pintype "passive"))
    )
    (net (code "101") (name "unconnected-(U18-SD-Pad46)") (class "Default")
      (node (ref "U18") (pin "46") (pinfunction "SD_46") (pintype "passive"))
    )
    (net (code "102") (name "unconnected-(U19-AVDD-Pad43)") (class "Default")
      (node (ref "U19") (pin "43") (pinfunction "AVDD_43") (pintype "passive"))
    )
    (net (code "103") (name "unconnected-(U19-AVDD-Pad45)") (class "Default")
      (node (ref "U19") (pin "45") (pinfunction "AVDD_45") (pintype "passive"))
    )
    (net (code "104") (name "unconnected-(U19-GPIO2{slash}DCLK-Pad9)") (class "Default")
      (node (ref "U19") (pin "9") (pinfunction "GPIO2/DCLK_9") (pintype "passive"))
    )
    (net (code "105") (name "unconnected-(U19-GPIO3{slash}SDATA-Pad10)") (class "Default")
      (node (ref "U19") (pin "10") (pinfunction "GPIO3/SDATA_10") (pintype "passive"))
    )
    (net (code "106") (name "unconnected-(U19-GPIO5{slash}I2S_MCLK-Pad25)") (class "Default")
      (node (ref "U19") (pin "25") (pinfunction "GPIO5/I2S_MCLK_25") (pintype "passive"))
    )
    (net (code "107") (name "unconnected-(U19-GPIO6{slash}I2S_SCLK-Pad11)") (class "Default")
      (node (ref "U19") (pin "11") (pinfunction "GPIO6/I2S_SCLK_11") (pintype "passive"))
    )
    (net (code "108") (name "unconnected-(U19-GPIO7{slash}I2S_SDATA-Pad12)") (class "Default")
      (node (ref "U19") (pin "12") (pinfunction "GPIO7/I2S_SDATA_12") (pintype "passive"))
    )
    (net (code "109") (name "unconnected-(U19-TX-Pad27)") (class "Default")
      (node (ref "U19") (pin "27") (pinfunction "TX_27") (pintype "passive"))
    )
    (net (code "110") (name "unconnected-(U19-VCO-Pad15)") (class "Default")
      (node (ref "U19") (pin "15") (pinfunction "VCO_15") (pintype "passive"))
    )
  )
)
